# BCM1.net
KiCad netlist of a schematic drawn in Altium Designer
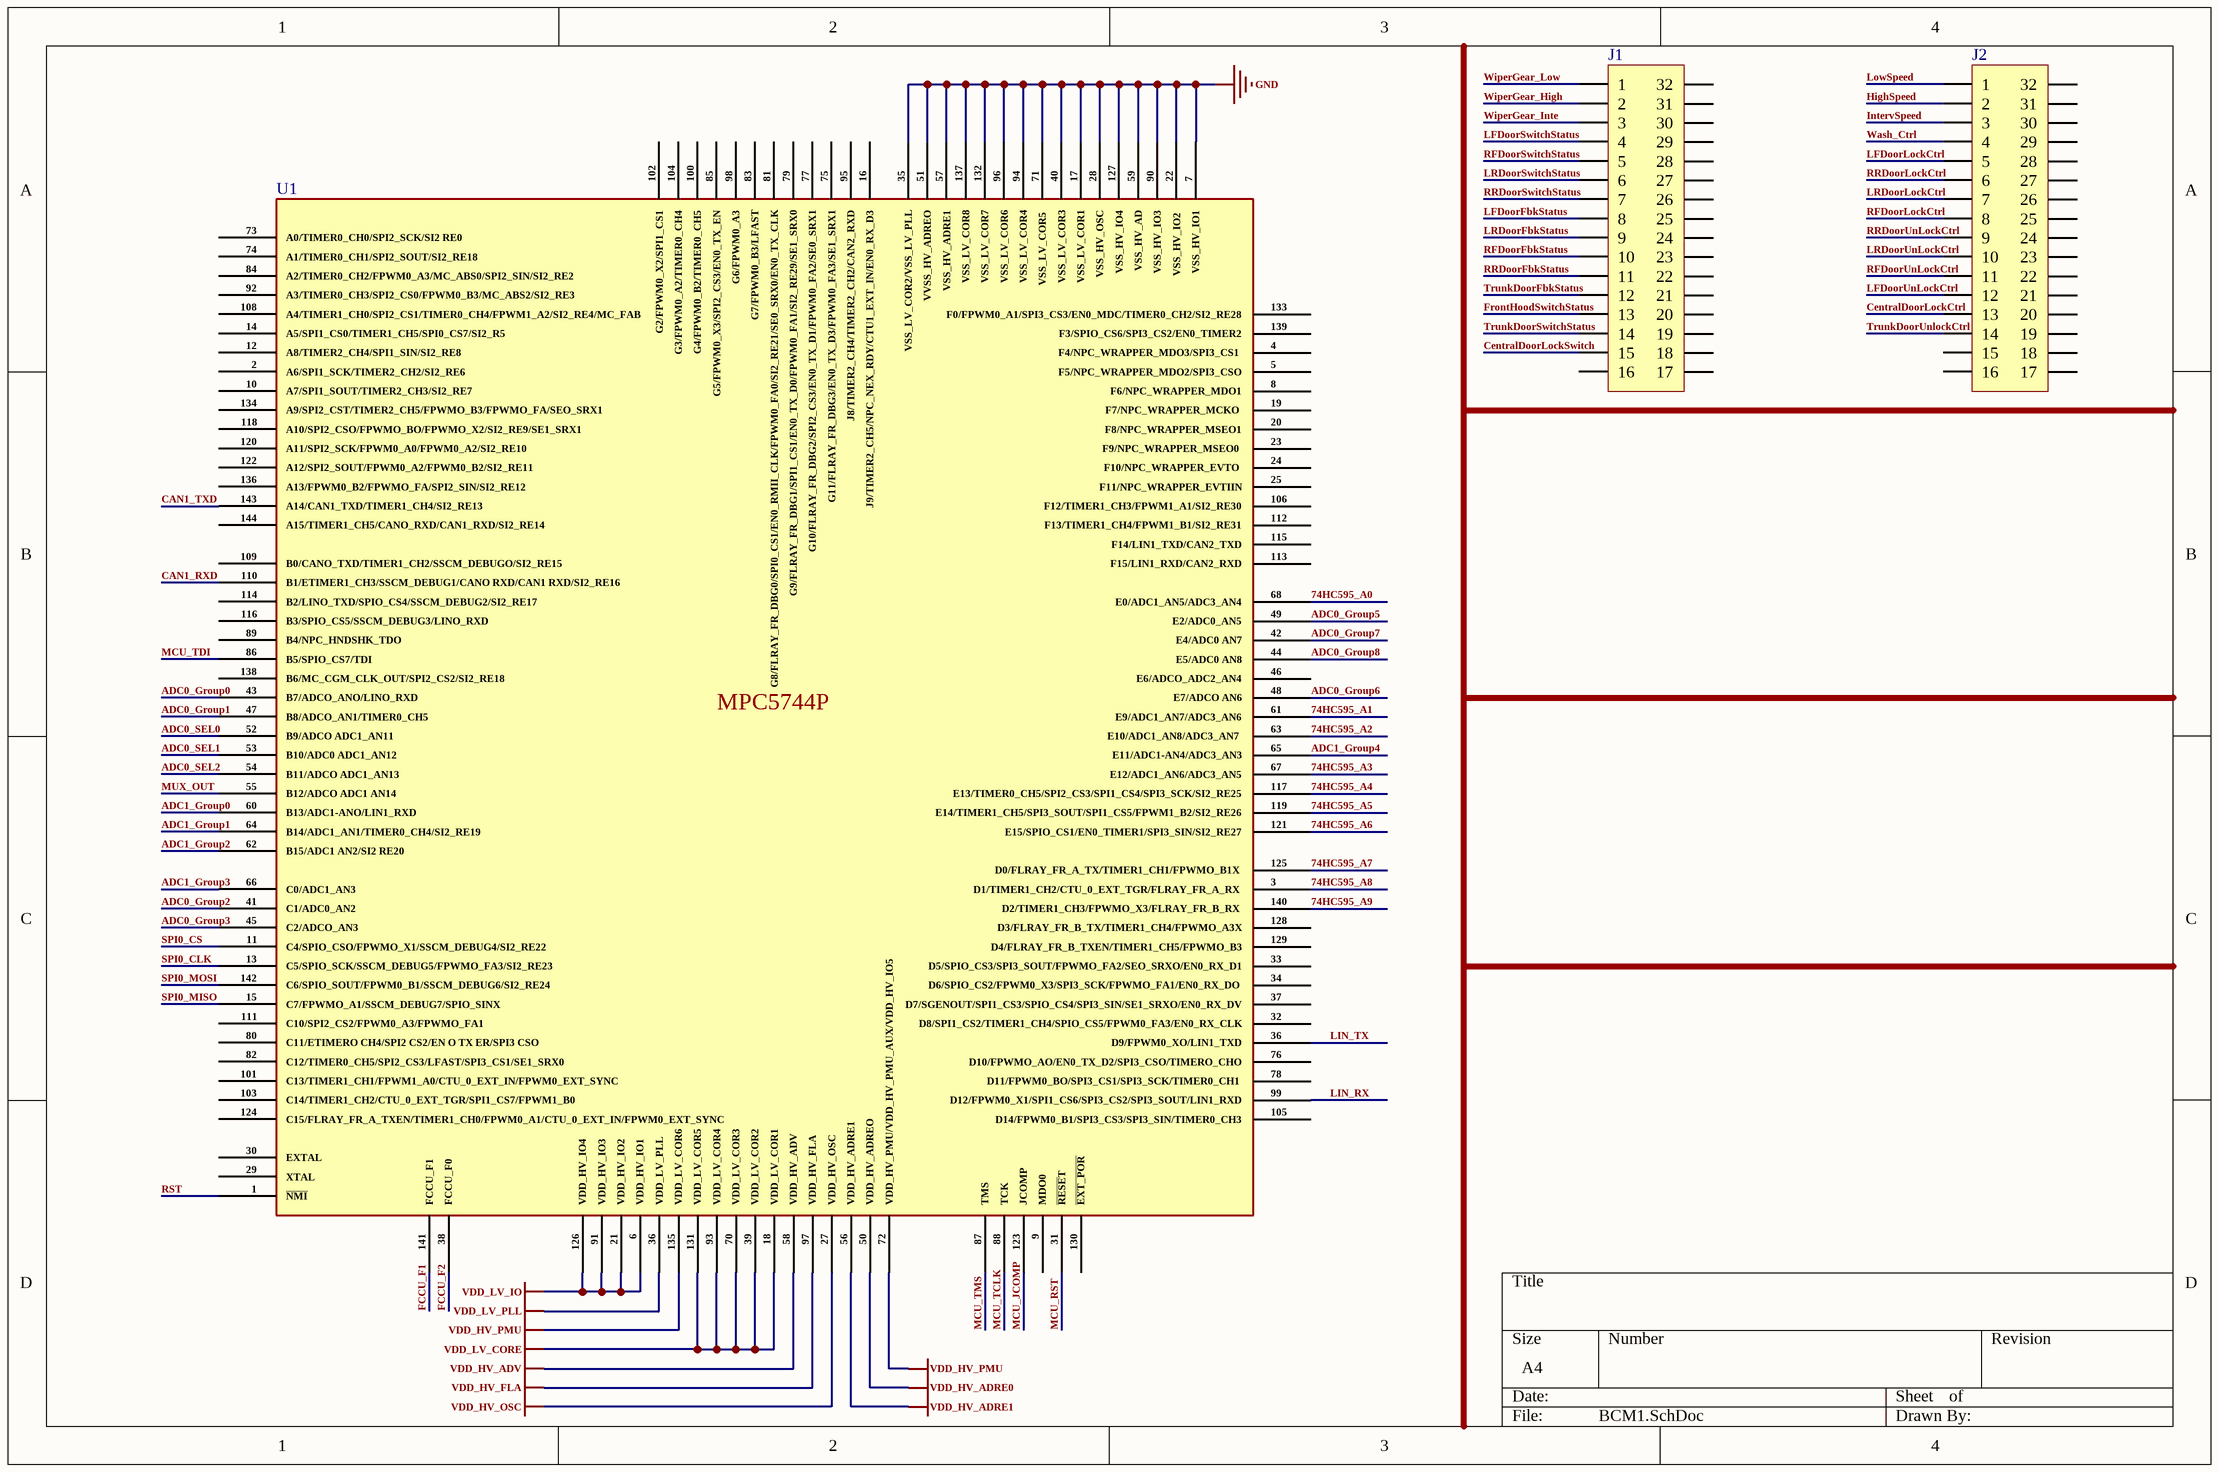
[diagram p0: BCM1.SchDoc]

(export (version "E")
  (design (tool "Eeschema 10.0.6"))
  (components
    (comp (ref "J1") (value "DIP32") (libsource (lib "BCM") (part "DIP32")))
    (comp (ref "J2") (value "DIP32") (libsource (lib "BCM") (part "DIP32")))
    (comp (ref "U1") (value "MPC5744PFK1AMLQ9") (libsource (lib "BCM") (part "MPC5744PFK1AMLQ9")))
  )
  (nets
    (net (code "1") (name "/74HC595_A0") (class "Default")
      (node (ref "U1") (pin "68") (pinfunction "E0/ADC1_AN5/ADC3_AN4_68") (pintype "passive"))
    )
    (net (code "2") (name "/74HC595_A1") (class "Default")
      (node (ref "U1") (pin "61") (pinfunction "E9/ADC1_AN7/ADC3_AN6_61") (pintype "passive"))
    )
    (net (code "3") (name "/74HC595_A2") (class "Default")
      (node (ref "U1") (pin "63") (pinfunction "E10/ADC1_AN8/ADC3_AN7_63") (pintype "passive"))
    )
    (net (code "4") (name "/74HC595_A3") (class "Default")
      (node (ref "U1") (pin "67") (pinfunction "E12/ADC1_AN6/ADC3_AN5_67") (pintype "passive"))
    )
    (net (code "5") (name "/74HC595_A4") (class "Default")
      (node (ref "U1") (pin "117") (pinfunction "E13/TIMER0_CH5/SPI2_CS3/SPI1_CS4/SPI3_SCK/SI2_RE25_117") (pintype "passive"))
    )
    (net (code "6") (name "/74HC595_A5") (class "Default")
      (node (ref "U1") (pin "119") (pinfunction "E14/TIMER1_CH5/SPI3_SOUT/SPI1_CS5/FPWM1_B2/SI2_RE26_119") (pintype "passive"))
    )
    (net (code "7") (name "/74HC595_A6") (class "Default")
      (node (ref "U1") (pin "121") (pinfunction "E15/SPIO_CS1/EN0_TIMER1/SPI3_SIN/SI2_RE27_121") (pintype "passive"))
    )
    (net (code "8") (name "/74HC595_A7") (class "Default")
      (node (ref "U1") (pin "125") (pinfunction "D0/FLRAY_FR_A_TX/TIMER1_CH1/FPWMO_B1X_125") (pintype "passive"))
    )
    (net (code "9") (name "/74HC595_A8") (class "Default")
      (node (ref "U1") (pin "3") (pinfunction "D1/TIMER1_CH2/CTU_0_EXT_TGR/FLRAY_FR_A_RX_3") (pintype "passive"))
    )
    (net (code "10") (name "/74HC595_A9") (class "Default")
      (node (ref "U1") (pin "140") (pinfunction "D2/TIMER1_CH3/FPWMO_X3/FLRAY_FR_B_RX_140") (pintype "passive"))
    )
    (net (code "11") (name "/ADC0_Group0") (class "Default")
      (node (ref "U1") (pin "43") (pinfunction "B7/ADCO_ANO/LINO_RXD_43") (pintype "passive"))
    )
    (net (code "12") (name "/ADC0_Group1") (class "Default")
      (node (ref "U1") (pin "47") (pinfunction "B8/ADCO_AN1/TIMER0_CH5_47") (pintype "passive"))
    )
    (net (code "13") (name "/ADC0_Group2") (class "Default")
      (node (ref "U1") (pin "41") (pinfunction "C1/ADC0_AN2_41") (pintype "passive"))
    )
    (net (code "14") (name "/ADC0_Group3") (class "Default")
      (node (ref "U1") (pin "45") (pinfunction "C2/ADCO_AN3_45") (pintype "passive"))
    )
    (net (code "15") (name "/ADC0_Group5") (class "Default")
      (node (ref "U1") (pin "49") (pinfunction "E2/ADC0_AN5_49") (pintype "passive"))
    )
    (net (code "16") (name "/ADC0_Group6") (class "Default")
      (node (ref "U1") (pin "48") (pinfunction "E7/ADCO_AN6_48") (pintype "passive"))
    )
    (net (code "17") (name "/ADC0_Group7") (class "Default")
      (node (ref "U1") (pin "42") (pinfunction "E4/ADC0_AN7_42") (pintype "passive"))
    )
    (net (code "18") (name "/ADC0_Group8") (class "Default")
      (node (ref "U1") (pin "44") (pinfunction "E5/ADC0_AN8_44") (pintype "passive"))
    )
    (net (code "19") (name "/ADC0_SEL0") (class "Default")
      (node (ref "U1") (pin "52") (pinfunction "B9/ADCO_ADC1_AN11_52") (pintype "passive"))
    )
    (net (code "20") (name "/ADC0_SEL1") (class "Default")
      (node (ref "U1") (pin "53") (pinfunction "B10/ADC0_ADC1_AN12_53") (pintype "passive"))
    )
    (net (code "21") (name "/ADC0_SEL2") (class "Default")
      (node (ref "U1") (pin "54") (pinfunction "B11/ADCO_ADC1_AN13_54") (pintype "passive"))
    )
    (net (code "22") (name "/ADC1_Group0") (class "Default")
      (node (ref "U1") (pin "60") (pinfunction "B13/ADC1-ANO/LIN1_RXD_60") (pintype "passive"))
    )
    (net (code "23") (name "/ADC1_Group1") (class "Default")
      (node (ref "U1") (pin "64") (pinfunction "B14/ADC1_AN1/TIMER0_CH4/SI2_RE19_64") (pintype "passive"))
    )
    (net (code "24") (name "/ADC1_Group2") (class "Default")
      (node (ref "U1") (pin "62") (pinfunction "B15/ADC1_AN2/SI2_RE20_62") (pintype "passive"))
    )
    (net (code "25") (name "/ADC1_Group3") (class "Default")
      (node (ref "U1") (pin "66") (pinfunction "C0/ADC1_AN3_66") (pintype "passive"))
    )
    (net (code "26") (name "/ADC1_Group4") (class "Default")
      (node (ref "U1") (pin "65") (pinfunction "E11/ADC1-AN4/ADC3_AN3_65") (pintype "passive"))
    )
    (net (code "27") (name "/CAN1_RXD") (class "Default")
      (node (ref "U1") (pin "110") (pinfunction "B1/ETIMER1_CH3/SSCM_DEBUG1/CANO_RXD/CAN1_RXD/SI2_RE16_110") (pintype "passive"))
    )
    (net (code "28") (name "/CAN1_TXD") (class "Default")
      (node (ref "U1") (pin "143") (pinfunction "A14/CAN1_TXD/TIMER1_CH4/SI2_RE13_143") (pintype "passive"))
    )
    (net (code "29") (name "/CentralDoorLockCtrl") (class "Default")
      (node (ref "J2") (pin "13") (pinfunction "13_13") (pintype "passive"))
    )
    (net (code "30") (name "/CentralDoorLockSwitch") (class "Default")
      (node (ref "J1") (pin "15") (pinfunction "15_15") (pintype "passive"))
    )
    (net (code "31") (name "/FCCU_F1") (class "Default")
      (node (ref "U1") (pin "141") (pinfunction "FCCU_F1_141") (pintype "passive"))
    )
    (net (code "32") (name "/FCCU_F2") (class "Default")
      (node (ref "U1") (pin "38") (pinfunction "FCCU_F0_38") (pintype "passive"))
    )
    (net (code "33") (name "/FrontHoodSwitchStatus") (class "Default")
      (node (ref "J1") (pin "13") (pinfunction "13_13") (pintype "passive"))
    )
    (net (code "34") (name "/HighSpeed") (class "Default")
      (node (ref "J2") (pin "2") (pinfunction "2_2") (pintype "passive"))
    )
    (net (code "35") (name "/IntervSpeed") (class "Default")
      (node (ref "J2") (pin "3") (pinfunction "3_3") (pintype "passive"))
    )
    (net (code "36") (name "/LFDoorFbkStatus") (class "Default")
      (node (ref "J1") (pin "8") (pinfunction "8_8") (pintype "passive"))
    )
    (net (code "37") (name "/LFDoorLockCtrl") (class "Default")
      (node (ref "J2") (pin "5") (pinfunction "5_5") (pintype "passive"))
    )
    (net (code "38") (name "/LFDoorSwitchStatus") (class "Default")
      (node (ref "J1") (pin "4") (pinfunction "4_4") (pintype "passive"))
    )
    (net (code "39") (name "/LFDoorUnLockCtrl") (class "Default")
      (node (ref "J2") (pin "12") (pinfunction "12_12") (pintype "passive"))
    )
    (net (code "40") (name "/LIN_RX") (class "Default")
      (node (ref "U1") (pin "99") (pinfunction "D12/FPWM0_X1/SPI1_CS6/SPI3_CS2/SPI3_SOUT/LIN1_RXD_99") (pintype "passive"))
    )
    (net (code "41") (name "/LIN_TX") (class "Default")
      (node (ref "U1") (pin "36") (pinfunction "D9/FPWM0_XO/LIN1_TXD_36") (pintype "passive"))
    )
    (net (code "42") (name "/LRDoorFbkStatus") (class "Default")
      (node (ref "J1") (pin "9") (pinfunction "9_9") (pintype "passive"))
    )
    (net (code "43") (name "/LRDoorLockCtrl") (class "Default")
      (node (ref "J2") (pin "7") (pinfunction "7_7") (pintype "passive"))
    )
    (net (code "44") (name "/LRDoorSwitchStatus") (class "Default")
      (node (ref "J1") (pin "6") (pinfunction "6_6") (pintype "passive"))
    )
    (net (code "45") (name "/LRDoorUnLockCtrl") (class "Default")
      (node (ref "J2") (pin "10") (pinfunction "10_10") (pintype "passive"))
    )
    (net (code "46") (name "/LowSpeed") (class "Default")
      (node (ref "J2") (pin "1") (pinfunction "1_1") (pintype "passive"))
    )
    (net (code "47") (name "/MCU_JCOMP") (class "Default")
      (node (ref "U1") (pin "123") (pinfunction "JCOMP_123") (pintype "passive"))
    )
    (net (code "48") (name "/MCU_RST") (class "Default")
      (node (ref "U1") (pin "31") (pinfunction "~{RESE}T_31") (pintype "passive"))
    )
    (net (code "49") (name "/MCU_TCLK") (class "Default")
      (node (ref "U1") (pin "88") (pinfunction "TCK_88") (pintype "passive"))
    )
    (net (code "50") (name "/MCU_TDI") (class "Default")
      (node (ref "U1") (pin "86") (pinfunction "B5/SPIO_CS7/TDI_86") (pintype "passive"))
    )
    (net (code "51") (name "/MCU_TMS") (class "Default")
      (node (ref "U1") (pin "87") (pinfunction "TMS_87") (pintype "passive"))
    )
    (net (code "52") (name "/MUX_OUT") (class "Default")
      (node (ref "U1") (pin "55") (pinfunction "B12/ADCO_ADC1_AN14_55") (pintype "passive"))
    )
    (net (code "53") (name "/RFDoorFbkStatus") (class "Default")
      (node (ref "J1") (pin "10") (pinfunction "10_10") (pintype "passive"))
    )
    (net (code "54") (name "/RFDoorLockCtrl") (class "Default")
      (node (ref "J2") (pin "8") (pinfunction "8_8") (pintype "passive"))
    )
    (net (code "55") (name "/RFDoorSwitchStatus") (class "Default")
      (node (ref "J1") (pin "5") (pinfunction "5_5") (pintype "passive"))
    )
    (net (code "56") (name "/RFDoorUnLockCtrl") (class "Default")
      (node (ref "J2") (pin "11") (pinfunction "11_11") (pintype "passive"))
    )
    (net (code "57") (name "/RRDoorFbkStatus") (class "Default")
      (node (ref "J1") (pin "11") (pinfunction "11_11") (pintype "passive"))
    )
    (net (code "58") (name "/RRDoorLockCtrl") (class "Default")
      (node (ref "J2") (pin "6") (pinfunction "6_6") (pintype "passive"))
    )
    (net (code "59") (name "/RRDoorSwitchStatus") (class "Default")
      (node (ref "J1") (pin "7") (pinfunction "7_7") (pintype "passive"))
    )
    (net (code "60") (name "/RRDoorUnLockCtrl") (class "Default")
      (node (ref "J2") (pin "9") (pinfunction "9_9") (pintype "passive"))
    )
    (net (code "61") (name "/RST") (class "Default")
      (node (ref "U1") (pin "1") (pinfunction "~{NMI}_1") (pintype "passive"))
    )
    (net (code "62") (name "/SPI0_CLK") (class "Default")
      (node (ref "U1") (pin "13") (pinfunction "C5/SPIO_SCK/SSCM_DEBUG5/FPWMO_FA3/SI2_RE23_13") (pintype "passive"))
    )
    (net (code "63") (name "/SPI0_CS") (class "Default")
      (node (ref "U1") (pin "11") (pinfunction "C4/SPIO_CSO/FPWMO_X1/SSCM_DEBUG4/SI2_RE22_11") (pintype "passive"))
    )
    (net (code "64") (name "/SPI0_MISO") (class "Default")
      (node (ref "U1") (pin "15") (pinfunction "C7/FPWMO_A1/SSCM_DEBUG7/SPIO_SINX_15") (pintype "passive"))
    )
    (net (code "65") (name "/SPI0_MOSI") (class "Default")
      (node (ref "U1") (pin "142") (pinfunction "C6/SPIO_SOUT/FPWM0_B1/SSCM_DEBUG6/SI2_RE24_142") (pintype "passive"))
    )
    (net (code "66") (name "/TrunkDoorFbkStatus") (class "Default")
      (node (ref "J1") (pin "12") (pinfunction "12_12") (pintype "passive"))
    )
    (net (code "67") (name "/TrunkDoorSwitchStatus") (class "Default")
      (node (ref "J1") (pin "14") (pinfunction "14_14") (pintype "passive"))
    )
    (net (code "68") (name "/TrunkDoorUnlockCtrl") (class "Default")
      (node (ref "J2") (pin "14") (pinfunction "14_14") (pintype "passive"))
    )
    (net (code "69") (name "/Wash_Ctrl") (class "Default")
      (node (ref "J2") (pin "4") (pinfunction "4_4") (pintype "passive"))
    )
    (net (code "70") (name "/WiperGear_High") (class "Default")
      (node (ref "J1") (pin "2") (pinfunction "2_2") (pintype "passive"))
    )
    (net (code "71") (name "/WiperGear_Inte") (class "Default")
      (node (ref "J1") (pin "3") (pinfunction "3_3") (pintype "passive"))
    )
    (net (code "72") (name "/WiperGear_Low") (class "Default")
      (node (ref "J1") (pin "1") (pinfunction "1_1") (pintype "passive"))
    )
    (net (code "73") (name "GND") (class "Default")
      (node (ref "U1") (pin "127") (pinfunction "VSS_HV_IO4_127") (pintype "passive"))
      (node (ref "U1") (pin "132") (pinfunction "VSS_LV_COR7_132") (pintype "passive"))
      (node (ref "U1") (pin "137") (pinfunction "VSS_LV_COR8_137") (pintype "passive"))
      (node (ref "U1") (pin "17") (pinfunction "VSS_LV_COR1_17") (pintype "passive"))
      (node (ref "U1") (pin "22") (pinfunction "VSS_HV_IO2_22") (pintype "passive"))
      (node (ref "U1") (pin "28") (pinfunction "VSS_HV_OSC_28") (pintype "passive"))
      (node (ref "U1") (pin "35") (pinfunction "VSS_LV_COR2/VSS_LV_PLL_35") (pintype "passive"))
      (node (ref "U1") (pin "40") (pinfunction "VSS_LV_COR3_40") (pintype "passive"))
      (node (ref "U1") (pin "51") (pinfunction "VVSS_HV_ADREO_51") (pintype "passive"))
      (node (ref "U1") (pin "57") (pinfunction "VSS_HV_ADRE1_57") (pintype "passive"))
      (node (ref "U1") (pin "59") (pinfunction "VSS_HV_AD_59") (pintype "passive"))
      (node (ref "U1") (pin "7") (pinfunction "VSS_HV_IO1_7") (pintype "passive"))
      (node (ref "U1") (pin "71") (pinfunction "VSS_LV_COR5_71") (pintype "passive"))
      (node (ref "U1") (pin "90") (pinfunction "VSS_HV_IO3_90") (pintype "passive"))
      (node (ref "U1") (pin "94") (pinfunction "VSS_LV_COR4_94") (pintype "passive"))
      (node (ref "U1") (pin "96") (pinfunction "VSS_LV_COR6_96") (pintype "passive"))
    )
    (net (code "74") (name "VDD_HV_ADRE0") (class "Default")
      (node (ref "U1") (pin "50") (pinfunction "VDD_HV_ADREO_50") (pintype "passive"))
    )
    (net (code "75") (name "VDD_HV_ADRE1") (class "Default")
      (node (ref "U1") (pin "56") (pinfunction "VDD_HV_ADRE1_56") (pintype "passive"))
    )
    (net (code "76") (name "VDD_HV_ADV") (class "Default")
      (node (ref "U1") (pin "58") (pinfunction "VDD_HV_ADV_58") (pintype "passive"))
    )
    (net (code "77") (name "VDD_HV_FLA") (class "Default")
      (node (ref "U1") (pin "97") (pinfunction "VDD_HV_FLA_97") (pintype "passive"))
    )
    (net (code "78") (name "VDD_HV_OSC") (class "Default")
      (node (ref "U1") (pin "27") (pinfunction "VDD_HV_OSC_27") (pintype "passive"))
    )
    (net (code "79") (name "VDD_HV_PMU") (class "Default")
      (node (ref "U1") (pin "135") (pinfunction "VDD_LV_COR6_135") (pintype "passive"))
      (node (ref "U1") (pin "72") (pinfunction "VDD_HV_PMU/VDD_HV_PMU_AUX/VDD_HV_IO5_72") (pintype "passive"))
    )
    (net (code "80") (name "VDD_LV_CORE") (class "Default")
      (node (ref "U1") (pin "131") (pinfunction "VDD_LV_COR5_131") (pintype "passive"))
      (node (ref "U1") (pin "18") (pinfunction "VDD_LV_COR1_18") (pintype "passive"))
      (node (ref "U1") (pin "39") (pinfunction "VDD_LV_COR2_39") (pintype "passive"))
      (node (ref "U1") (pin "70") (pinfunction "VDD_LV_COR3_70") (pintype "passive"))
      (node (ref "U1") (pin "93") (pinfunction "VDD_LV_COR4_93") (pintype "passive"))
    )
    (net (code "81") (name "VDD_LV_IO") (class "Default")
      (node (ref "U1") (pin "126") (pinfunction "VDD_HV_IO4_126") (pintype "passive"))
      (node (ref "U1") (pin "21") (pinfunction "VDD_HV_IO2_21") (pintype "passive"))
      (node (ref "U1") (pin "6") (pinfunction "VDD_HV_IO1_6") (pintype "passive"))
      (node (ref "U1") (pin "91") (pinfunction "VDD_HV_IO3_91") (pintype "passive"))
    )
    (net (code "82") (name "VDD_LV_PLL") (class "Default")
      (node (ref "U1") (pin "36") (pinfunction "VDD_LV_PLL_36") (pintype "passive"))
    )
    (net (code "83") (name "unconnected-(J1-Pad16)") (class "Default")
      (node (ref "J1") (pin "16") (pinfunction "16_16") (pintype "passive"))
    )
    (net (code "84") (name "unconnected-(J1-Pad17)") (class "Default")
      (node (ref "J1") (pin "17") (pinfunction "17_17") (pintype "passive"))
    )
    (net (code "85") (name "unconnected-(J1-Pad18)") (class "Default")
      (node (ref "J1") (pin "18") (pinfunction "18_18") (pintype "passive"))
    )
    (net (code "86") (name "unconnected-(J1-Pad19)") (class "Default")
      (node (ref "J1") (pin "19") (pinfunction "19_19") (pintype "passive"))
    )
    (net (code "87") (name "unconnected-(J1-Pad20)") (class "Default")
      (node (ref "J1") (pin "20") (pinfunction "20_20") (pintype "passive"))
    )
    (net (code "88") (name "unconnected-(J1-Pad21)") (class "Default")
      (node (ref "J1") (pin "21") (pinfunction "21_21") (pintype "passive"))
    )
    (net (code "89") (name "unconnected-(J1-Pad22)") (class "Default")
      (node (ref "J1") (pin "22") (pinfunction "22_22") (pintype "passive"))
    )
    (net (code "90") (name "unconnected-(J1-Pad23)") (class "Default")
      (node (ref "J1") (pin "23") (pinfunction "23_23") (pintype "passive"))
    )
    (net (code "91") (name "unconnected-(J1-Pad24)") (class "Default")
      (node (ref "J1") (pin "24") (pinfunction "24_24") (pintype "passive"))
    )
    (net (code "92") (name "unconnected-(J1-Pad25)") (class "Default")
      (node (ref "J1") (pin "25") (pinfunction "25_25") (pintype "passive"))
    )
    (net (code "93") (name "unconnected-(J1-Pad26)") (class "Default")
      (node (ref "J1") (pin "26") (pinfunction "26_26") (pintype "passive"))
    )
    (net (code "94") (name "unconnected-(J1-Pad27)") (class "Default")
      (node (ref "J1") (pin "27") (pinfunction "27_27") (pintype "passive"))
    )
    (net (code "95") (name "unconnected-(J1-Pad28)") (class "Default")
      (node (ref "J1") (pin "28") (pinfunction "28_28") (pintype "passive"))
    )
    (net (code "96") (name "unconnected-(J1-Pad29)") (class "Default")
      (node (ref "J1") (pin "29") (pinfunction "29_29") (pintype "passive"))
    )
    (net (code "97") (name "unconnected-(J1-Pad30)") (class "Default")
      (node (ref "J1") (pin "30") (pinfunction "30_30") (pintype "passive"))
    )
    (net (code "98") (name "unconnected-(J1-Pad31)") (class "Default")
      (node (ref "J1") (pin "31") (pinfunction "31_31") (pintype "passive"))
    )
    (net (code "99") (name "unconnected-(J1-Pad32)") (class "Default")
      (node (ref "J1") (pin "32") (pinfunction "32_32") (pintype "passive"))
    )
    (net (code "100") (name "unconnected-(J2-Pad15)") (class "Default")
      (node (ref "J2") (pin "15") (pinfunction "15_15") (pintype "passive"))
    )
    (net (code "101") (name "unconnected-(J2-Pad16)") (class "Default")
      (node (ref "J2") (pin "16") (pinfunction "16_16") (pintype "passive"))
    )
    (net (code "102") (name "unconnected-(J2-Pad17)") (class "Default")
      (node (ref "J2") (pin "17") (pinfunction "17_17") (pintype "passive"))
    )
    (net (code "103") (name "unconnected-(J2-Pad18)") (class "Default")
      (node (ref "J2") (pin "18") (pinfunction "18_18") (pintype "passive"))
    )
    (net (code "104") (name "unconnected-(J2-Pad19)") (class "Default")
      (node (ref "J2") (pin "19") (pinfunction "19_19") (pintype "passive"))
    )
    (net (code "105") (name "unconnected-(J2-Pad20)") (class "Default")
      (node (ref "J2") (pin "20") (pinfunction "20_20") (pintype "passive"))
    )
    (net (code "106") (name "unconnected-(J2-Pad21)") (class "Default")
      (node (ref "J2") (pin "21") (pinfunction "21_21") (pintype "passive"))
    )
    (net (code "107") (name "unconnected-(J2-Pad22)") (class "Default")
      (node (ref "J2") (pin "22") (pinfunction "22_22") (pintype "passive"))
    )
    (net (code "108") (name "unconnected-(J2-Pad23)") (class "Default")
      (node (ref "J2") (pin "23") (pinfunction "23_23") (pintype "passive"))
    )
    (net (code "109") (name "unconnected-(J2-Pad24)") (class "Default")
      (node (ref "J2") (pin "24") (pinfunction "24_24") (pintype "passive"))
    )
    (net (code "110") (name "unconnected-(J2-Pad25)") (class "Default")
      (node (ref "J2") (pin "25") (pinfunction "25_25") (pintype "passive"))
    )
    (net (code "111") (name "unconnected-(J2-Pad26)") (class "Default")
      (node (ref "J2") (pin "26") (pinfunction "26_26") (pintype "passive"))
    )
    (net (code "112") (name "unconnected-(J2-Pad27)") (class "Default")
      (node (ref "J2") (pin "27") (pinfunction "27_27") (pintype "passive"))
    )
    (net (code "113") (name "unconnected-(J2-Pad28)") (class "Default")
      (node (ref "J2") (pin "28") (pinfunction "28_28") (pintype "passive"))
    )
    (net (code "114") (name "unconnected-(J2-Pad29)") (class "Default")
      (node (ref "J2") (pin "29") (pinfunction "29_29") (pintype "passive"))
    )
    (net (code "115") (name "unconnected-(J2-Pad30)") (class "Default")
      (node (ref "J2") (pin "30") (pinfunction "30_30") (pintype "passive"))
    )
    (net (code "116") (name "unconnected-(J2-Pad31)") (class "Default")
      (node (ref "J2") (pin "31") (pinfunction "31_31") (pintype "passive"))
    )
    (net (code "117") (name "unconnected-(J2-Pad32)") (class "Default")
      (node (ref "J2") (pin "32") (pinfunction "32_32") (pintype "passive"))
    )
    (net (code "118") (name "unconnected-(U1-A0{slash}TIMER0_CH0{slash}SPI2_SCK{slash}SI2_RE0-Pad73)") (class "Default")
      (node (ref "U1") (pin "73") (pinfunction "A0/TIMER0_CH0/SPI2_SCK/SI2_RE0_73") (pintype "passive"))
    )
    (net (code "119") (name "unconnected-(U1-A1{slash}TIMER0_CH1{slash}SPI2_SOUT{slash}SI2_RE18-Pad74)") (class "Default")
      (node (ref "U1") (pin "74") (pinfunction "A1/TIMER0_CH1/SPI2_SOUT/SI2_RE18_74") (pintype "passive"))
    )
    (net (code "120") (name "unconnected-(U1-A2{slash}TIMER0_CH2{slash}FPWM0_A3{slash}MC_ABS0{slash}SPI2_SIN{slash}SI2_RE2-Pad84)") (class "Default")
      (node (ref "U1") (pin "84") (pinfunction "A2/TIMER0_CH2/FPWM0_A3/MC_ABS0/SPI2_SIN/SI2_RE2_84") (pintype "passive"))
    )
    (net (code "121") (name "unconnected-(U1-A3{slash}TIMER0_CH3{slash}SPI2_CS0{slash}FPWM0_B3{slash}MC_ABS2{slash}SI2_RE3-Pad92)") (class "Default")
      (node (ref "U1") (pin "92") (pinfunction "A3/TIMER0_CH3/SPI2_CS0/FPWM0_B3/MC_ABS2/SI2_RE3_92") (pintype "passive"))
    )
    (net (code "122") (name "unconnected-(U1-A4{slash}TIMER1_CH0{slash}SPI2_CS1{slash}TIMER0_CH4{slash}FPWM1_A2{slash}SI2_RE4{slash}MC_FAB-Pad108)") (class "Default")
      (node (ref "U1") (pin "108") (pinfunction "A4/TIMER1_CH0/SPI2_CS1/TIMER0_CH4/FPWM1_A2/SI2_RE4/MC_FAB_108") (pintype "passive"))
    )
    (net (code "123") (name "unconnected-(U1-A5{slash}SPI1_CS0{slash}TIMER1_CH5{slash}SPI0_CS7{slash}SI2_R5-Pad14)") (class "Default")
      (node (ref "U1") (pin "14") (pinfunction "A5/SPI1_CS0/TIMER1_CH5/SPI0_CS7/SI2_R5_14") (pintype "passive"))
    )
    (net (code "124") (name "unconnected-(U1-A6{slash}SPI1_SCK{slash}TIMER2_CH2{slash}SI2_RE6-Pad2)") (class "Default")
      (node (ref "U1") (pin "2") (pinfunction "A6/SPI1_SCK/TIMER2_CH2/SI2_RE6_2") (pintype "passive"))
    )
    (net (code "125") (name "unconnected-(U1-A7{slash}SPI1_SOUT{slash}TIMER2_CH3{slash}SI2_RE7-Pad10)") (class "Default")
      (node (ref "U1") (pin "10") (pinfunction "A7/SPI1_SOUT/TIMER2_CH3/SI2_RE7_10") (pintype "passive"))
    )
    (net (code "126") (name "unconnected-(U1-A8{slash}TIMER2_CH4{slash}SPI1_SIN{slash}SI2_RE8-Pad12)") (class "Default")
      (node (ref "U1") (pin "12") (pinfunction "A8/TIMER2_CH4/SPI1_SIN/SI2_RE8_12") (pintype "passive"))
    )
    (net (code "127") (name "unconnected-(U1-A9{slash}SPI2_CST{slash}TIMER2_CH5{slash}FPWMO_B3{slash}FPWMO_FA{slash}SEO_SRX1-Pad134)") (class "Default")
      (node (ref "U1") (pin "134") (pinfunction "A9/SPI2_CST/TIMER2_CH5/FPWMO_B3/FPWMO_FA/SEO_SRX1_134") (pintype "passive"))
    )
    (net (code "128") (name "unconnected-(U1-A10{slash}SPI2_CSO{slash}FPWMO_BO{slash}FPWMO_X2{slash}SI2_RE9{slash}SE1_SRX1-Pad118)") (class "Default")
      (node (ref "U1") (pin "118") (pinfunction "A10/SPI2_CSO/FPWMO_BO/FPWMO_X2/SI2_RE9/SE1_SRX1_118") (pintype "passive"))
    )
    (net (code "129") (name "unconnected-(U1-A11{slash}SPI2_SCK{slash}FPWM0_A0{slash}FPWM0_A2{slash}SI2_RE10-Pad120)") (class "Default")
      (node (ref "U1") (pin "120") (pinfunction "A11/SPI2_SCK/FPWM0_A0/FPWM0_A2/SI2_RE10_120") (pintype "passive"))
    )
    (net (code "130") (name "unconnected-(U1-A12{slash}SPI2_SOUT{slash}FPWM0_A2{slash}FPWM0_B2{slash}SI2_RE11-Pad122)") (class "Default")
      (node (ref "U1") (pin "122") (pinfunction "A12/SPI2_SOUT/FPWM0_A2/FPWM0_B2/SI2_RE11_122") (pintype "passive"))
    )
    (net (code "131") (name "unconnected-(U1-A13{slash}FPWM0_B2{slash}FPWMO_FA{slash}SPI2_SIN{slash}SI2_RE12-Pad136)") (class "Default")
      (node (ref "U1") (pin "136") (pinfunction "A13/FPWM0_B2/FPWMO_FA/SPI2_SIN/SI2_RE12_136") (pintype "passive"))
    )
    (net (code "132") (name "unconnected-(U1-A15{slash}TIMER1_CH5{slash}CANO_RXD{slash}CAN1_RXD{slash}SI2_RE14-Pad144)") (class "Default")
      (node (ref "U1") (pin "144") (pinfunction "A15/TIMER1_CH5/CANO_RXD/CAN1_RXD/SI2_RE14_144") (pintype "passive"))
    )
    (net (code "133") (name "unconnected-(U1-B0{slash}CANO_TXD{slash}TIMER1_CH2{slash}SSCM_DEBUGO{slash}SI2_RE15-Pad109)") (class "Default")
      (node (ref "U1") (pin "109") (pinfunction "B0/CANO_TXD/TIMER1_CH2/SSCM_DEBUGO/SI2_RE15_109") (pintype "passive"))
    )
    (net (code "134") (name "unconnected-(U1-B2{slash}LINO_TXD{slash}SPIO_CS4{slash}SSCM_DEBUG2{slash}SI2_RE17-Pad114)") (class "Default")
      (node (ref "U1") (pin "114") (pinfunction "B2/LINO_TXD/SPIO_CS4/SSCM_DEBUG2/SI2_RE17_114") (pintype "passive"))
    )
    (net (code "135") (name "unconnected-(U1-B3{slash}SPIO_CS5{slash}SSCM_DEBUG3{slash}LINO_RXD-Pad116)") (class "Default")
      (node (ref "U1") (pin "116") (pinfunction "B3/SPIO_CS5/SSCM_DEBUG3/LINO_RXD_116") (pintype "passive"))
    )
    (net (code "136") (name "unconnected-(U1-B4{slash}NPC_HNDSHK_TDO-Pad89)") (class "Default")
      (node (ref "U1") (pin "89") (pinfunction "B4/NPC_HNDSHK_TDO_89") (pintype "passive"))
    )
    (net (code "137") (name "unconnected-(U1-B6{slash}MC_CGM_CLK_OUT{slash}SPI2_CS2{slash}SI2_RE18-Pad138)") (class "Default")
      (node (ref "U1") (pin "138") (pinfunction "B6/MC_CGM_CLK_OUT/SPI2_CS2/SI2_RE18_138") (pintype "passive"))
    )
    (net (code "138") (name "unconnected-(U1-C10{slash}SPI2_CS2{slash}FPWM0_A3{slash}FPWMO_FA1-Pad111)") (class "Default")
      (node (ref "U1") (pin "111") (pinfunction "C10/SPI2_CS2/FPWM0_A3/FPWMO_FA1_111") (pintype "passive"))
    )
    (net (code "139") (name "unconnected-(U1-C11{slash}ETIMERO_CH4{slash}SPI2_CS2{slash}EN_O_TX_ER{slash}SPI3_CSO-Pad80)") (class "Default")
      (node (ref "U1") (pin "80") (pinfunction "C11/ETIMERO_CH4/SPI2_CS2/EN_O_TX_ER/SPI3_CSO_80") (pintype "passive"))
    )
    (net (code "140") (name "unconnected-(U1-C12{slash}TIMER0_CH5{slash}SPI2_CS3{slash}LFAST{slash}SPI3_CS1{slash}SE1_SRX0-Pad82)") (class "Default")
      (node (ref "U1") (pin "82") (pinfunction "C12/TIMER0_CH5/SPI2_CS3/LFAST/SPI3_CS1/SE1_SRX0_82") (pintype "passive"))
    )
    (net (code "141") (name "unconnected-(U1-C13{slash}TIMER1_CH1{slash}FPWM1_A0{slash}CTU_0_EXT_IN{slash}FPWM0_EXT_SYNC-Pad101)") (class "Default")
      (node (ref "U1") (pin "101") (pinfunction "C13/TIMER1_CH1/FPWM1_A0/CTU_0_EXT_IN/FPWM0_EXT_SYNC_101") (pintype "passive"))
    )
    (net (code "142") (name "unconnected-(U1-C14{slash}TIMER1_CH2{slash}CTU_0_EXT_TGR{slash}SPI1_CS7{slash}FPWM1_B0-Pad103)") (class "Default")
      (node (ref "U1") (pin "103") (pinfunction "C14/TIMER1_CH2/CTU_0_EXT_TGR/SPI1_CS7/FPWM1_B0_103") (pintype "passive"))
    )
    (net (code "143") (name "unconnected-(U1-C15{slash}FLRAY_FR_A_TXEN{slash}TIMER1_CH0{slash}FPWM0_A1{slash}CTU_0_EXT_IN{slash}FPWM0_EXT_SYNC-Pad124)") (class "Default")
      (node (ref "U1") (pin "124") (pinfunction "C15/FLRAY_FR_A_TXEN/TIMER1_CH0/FPWM0_A1/CTU_0_EXT_IN/FPWM0_EXT_SYNC_124") (pintype "passive"))
    )
    (net (code "144") (name "unconnected-(U1-D3{slash}FLRAY_FR_B_TX{slash}TIMER1_CH4{slash}FPWMO_A3X-Pad128)") (class "Default")
      (node (ref "U1") (pin "128") (pinfunction "D3/FLRAY_FR_B_TX/TIMER1_CH4/FPWMO_A3X_128") (pintype "passive"))
    )
    (net (code "145") (name "unconnected-(U1-D4{slash}FLRAY_FR_B_TXEN{slash}TIMER1_CH5{slash}FPWMO_B3-Pad129)") (class "Default")
      (node (ref "U1") (pin "129") (pinfunction "D4/FLRAY_FR_B_TXEN/TIMER1_CH5/FPWMO_B3_129") (pintype "passive"))
    )
    (net (code "146") (name "unconnected-(U1-D5{slash}SPIO_CS3{slash}SPI3_SOUT{slash}FPWMO_FA2{slash}SEO_SRXO{slash}EN0_RX_D1-Pad33)") (class "Default")
      (node (ref "U1") (pin "33") (pinfunction "D5/SPIO_CS3/SPI3_SOUT/FPWMO_FA2/SEO_SRXO/EN0_RX_D1_33") (pintype "passive"))
    )
    (net (code "147") (name "unconnected-(U1-D6{slash}SPIO_CS2{slash}FPWM0_X3{slash}SPI3_SCK{slash}FPWMO_FA1{slash}EN0_RX_DO-Pad34)") (class "Default")
      (node (ref "U1") (pin "34") (pinfunction "D6/SPIO_CS2/FPWM0_X3/SPI3_SCK/FPWMO_FA1/EN0_RX_DO_34") (pintype "passive"))
    )
    (net (code "148") (name "unconnected-(U1-D7{slash}SGENOUT{slash}SPI1_CS3{slash}SPIO_CS4{slash}SPI3_SIN{slash}SE1_SRXO{slash}EN0_RX_DV-Pad37)") (class "Default")
      (node (ref "U1") (pin "37") (pinfunction "D7/SGENOUT/SPI1_CS3/SPIO_CS4/SPI3_SIN/SE1_SRXO/EN0_RX_DV_37") (pintype "passive"))
    )
    (net (code "149") (name "unconnected-(U1-D8{slash}SPI1_CS2{slash}TIMER1_CH4{slash}SPIO_CS5{slash}FPWM0_FA3{slash}EN0_RX_CLK-Pad32)") (class "Default")
      (node (ref "U1") (pin "32") (pinfunction "D8/SPI1_CS2/TIMER1_CH4/SPIO_CS5/FPWM0_FA3/EN0_RX_CLK_32") (pintype "passive"))
    )
    (net (code "150") (name "unconnected-(U1-D10{slash}FPWMO_AO{slash}EN0_TX_D2{slash}SPI3_CSO{slash}TIMERO_CHO-Pad76)") (class "Default")
      (node (ref "U1") (pin "76") (pinfunction "D10/FPWMO_AO/EN0_TX_D2/SPI3_CSO/TIMERO_CHO_76") (pintype "passive"))
    )
    (net (code "151") (name "unconnected-(U1-D11{slash}FPWM0_BO{slash}SPI3_CS1{slash}SPI3_SCK{slash}TIMER0_CH1-Pad78)") (class "Default")
      (node (ref "U1") (pin "78") (pinfunction "D11/FPWM0_BO/SPI3_CS1/SPI3_SCK/TIMER0_CH1_78") (pintype "passive"))
    )
    (net (code "152") (name "unconnected-(U1-D14{slash}FPWM0_B1{slash}SPI3_CS3{slash}SPI3_SIN{slash}TIMER0_CH3-Pad105)") (class "Default")
      (node (ref "U1") (pin "105") (pinfunction "D14/FPWM0_B1/SPI3_CS3/SPI3_SIN/TIMER0_CH3_105") (pintype "passive"))
    )
    (net (code "153") (name "unconnected-(U1-E6{slash}ADCO_ADC2_AN4-Pad46)") (class "Default")
      (node (ref "U1") (pin "46") (pinfunction "E6/ADCO_ADC2_AN4_46") (pintype "passive"))
    )
    (net (code "154") (name "unconnected-(U1-EXTAL-Pad30)") (class "Default")
      (node (ref "U1") (pin "30") (pinfunction "EXTAL_30") (pintype "passive"))
    )
    (net (code "155") (name "unconnected-(U1-F0{slash}FPWM0_A1{slash}SPI3_CS3{slash}EN0_MDC{slash}TIMER0_CH2{slash}SI2_RE28-Pad133)") (class "Default")
      (node (ref "U1") (pin "133") (pinfunction "F0/FPWM0_A1/SPI3_CS3/EN0_MDC/TIMER0_CH2/SI2_RE28_133") (pintype "passive"))
    )
    (net (code "156") (name "unconnected-(U1-F3{slash}SPIO_CS6{slash}SPI3_CS2{slash}EN0_TIMER2-Pad139)") (class "Default")
      (node (ref "U1") (pin "139") (pinfunction "F3/SPIO_CS6/SPI3_CS2/EN0_TIMER2_139") (pintype "passive"))
    )
    (net (code "157") (name "unconnected-(U1-F4{slash}NPC_WRAPPER_MDO3{slash}SPI3_CS1-Pad4)") (class "Default")
      (node (ref "U1") (pin "4") (pinfunction "F4/NPC_WRAPPER_MDO3/SPI3_CS1_4") (pintype "passive"))
    )
    (net (code "158") (name "unconnected-(U1-F5{slash}NPC_WRAPPER_MDO2{slash}SPI3_CSO-Pad5)") (class "Default")
      (node (ref "U1") (pin "5") (pinfunction "F5/NPC_WRAPPER_MDO2/SPI3_CSO_5") (pintype "passive"))
    )
    (net (code "159") (name "unconnected-(U1-F6{slash}NPC_WRAPPER_MDO1-Pad8)") (class "Default")
      (node (ref "U1") (pin "8") (pinfunction "F6/NPC_WRAPPER_MDO1_8") (pintype "passive"))
    )
    (net (code "160") (name "unconnected-(U1-F7{slash}NPC_WRAPPER_MCKO-Pad19)") (class "Default")
      (node (ref "U1") (pin "19") (pinfunction "F7/NPC_WRAPPER_MCKO_19") (pintype "passive"))
    )
    (net (code "161") (name "unconnected-(U1-F8{slash}NPC_WRAPPER_MSEO1-Pad20)") (class "Default")
      (node (ref "U1") (pin "20") (pinfunction "F8/NPC_WRAPPER_MSEO1_20") (pintype "passive"))
    )
    (net (code "162") (name "unconnected-(U1-F9{slash}NPC_WRAPPER_MSEO0-Pad23)") (class "Default")
      (node (ref "U1") (pin "23") (pinfunction "F9/NPC_WRAPPER_MSEO0_23") (pintype "passive"))
    )
    (net (code "163") (name "unconnected-(U1-F10{slash}NPC_WRAPPER_EVTO-Pad24)") (class "Default")
      (node (ref "U1") (pin "24") (pinfunction "F10/NPC_WRAPPER_EVTO_24") (pintype "passive"))
    )
    (net (code "164") (name "unconnected-(U1-F11{slash}NPC_WRAPPER_EVTIIN-Pad25)") (class "Default")
      (node (ref "U1") (pin "25") (pinfunction "F11/NPC_WRAPPER_EVTIIN_25") (pintype "passive"))
    )
    (net (code "165") (name "unconnected-(U1-F12{slash}TIMER1_CH3{slash}FPWM1_A1{slash}SI2_RE30-Pad106)") (class "Default")
      (node (ref "U1") (pin "106") (pinfunction "F12/TIMER1_CH3/FPWM1_A1/SI2_RE30_106") (pintype "passive"))
    )
    (net (code "166") (name "unconnected-(U1-F13{slash}TIMER1_CH4{slash}FPWM1_B1{slash}SI2_RE31-Pad112)") (class "Default")
      (node (ref "U1") (pin "112") (pinfunction "F13/TIMER1_CH4/FPWM1_B1/SI2_RE31_112") (pintype "passive"))
    )
    (net (code "167") (name "unconnected-(U1-F14{slash}LIN1_TXD{slash}CAN2_TXD-Pad115)") (class "Default")
      (node (ref "U1") (pin "115") (pinfunction "F14/LIN1_TXD/CAN2_TXD_115") (pintype "passive"))
    )
    (net (code "168") (name "unconnected-(U1-F15{slash}LIN1_RXD{slash}CAN2_RXD-Pad113)") (class "Default")
      (node (ref "U1") (pin "113") (pinfunction "F15/LIN1_RXD/CAN2_RXD_113") (pintype "passive"))
    )
    (net (code "169") (name "unconnected-(U1-G2{slash}FPWM0_X2{slash}SPI1_CS1-Pad102)") (class "Default")
      (node (ref "U1") (pin "102") (pinfunction "G2/FPWM0_X2/SPI1_CS1_102") (pintype "passive"))
    )
    (net (code "170") (name "unconnected-(U1-G3{slash}FPWM0_A2{slash}TIMER0_CH4-Pad104)") (class "Default")
      (node (ref "U1") (pin "104") (pinfunction "G3/FPWM0_A2/TIMER0_CH4_104") (pintype "passive"))
    )
    (net (code "171") (name "unconnected-(U1-G4{slash}FPWM0_B2{slash}TIMER0_CH5-Pad100)") (class "Default")
      (node (ref "U1") (pin "100") (pinfunction "G4/FPWM0_B2/TIMER0_CH5_100") (pintype "passive"))
    )
    (net (code "172") (name "unconnected-(U1-G5{slash}FPWM0_X3{slash}SPI2_CS3{slash}EN0_TX_EN-Pad85)") (class "Default")
      (node (ref "U1") (pin "85") (pinfunction "G5/FPWM0_X3/SPI2_CS3/EN0_TX_EN_85") (pintype "passive"))
    )
    (net (code "173") (name "unconnected-(U1-G6{slash}FPWM0_A3-Pad98)") (class "Default")
      (node (ref "U1") (pin "98") (pinfunction "G6/FPWM0_A3_98") (pintype "passive"))
    )
    (net (code "174") (name "unconnected-(U1-G7{slash}FPWM0_B3{slash}LFAST-Pad83)") (class "Default")
      (node (ref "U1") (pin "83") (pinfunction "G7/FPWM0_B3/LFAST_83") (pintype "passive"))
    )
    (net (code "175") (name "unconnected-(U1-G8{slash}FLRAY_FR_DBG0{slash}SPI0_CS1{slash}EN0_RMII_CLK{slash}FPWM0_FA0{slash}SI2_RE21{slash}SE0_SRX0{slash}EN0_TX_CLK-Pad81)") (class "Default")
      (node (ref "U1") (pin "81") (pinfunction "G8/FLRAY_FR_DBG0/SPI0_CS1/EN0_RMII_CLK/FPWM0_FA0/SI2_RE21/SE0_SRX0/EN0_TX_CLK_81") (pintype "passive"))
    )
    (net (code "176") (name "unconnected-(U1-G9{slash}FLRAY_FR_DBG1{slash}SPI1_CS1{slash}EN0_TX_D0{slash}FPWM0_FA1{slash}SI2_RE29{slash}SE1_SRX0-Pad79)") (class "Default")
      (node (ref "U1") (pin "79") (pinfunction "G9/FLRAY_FR_DBG1/SPI1_CS1/EN0_TX_D0/FPWM0_FA1/SI2_RE29/SE1_SRX0_79") (pintype "passive"))
    )
    (net (code "177") (name "unconnected-(U1-G10{slash}FLRAY_FR_DBG2{slash}SPI2_CS3{slash}EN0_TX_D1{slash}FPWM0_FA2{slash}SE0_SRX1-Pad77)") (class "Default")
      (node (ref "U1") (pin "77") (pinfunction "G10/FLRAY_FR_DBG2/SPI2_CS3/EN0_TX_D1/FPWM0_FA2/SE0_SRX1_77") (pintype "passive"))
    )
    (net (code "178") (name "unconnected-(U1-G11{slash}FLRAY_FR_DBG3{slash}EN0_TX_D3{slash}FPWM0_FA3{slash}SE1_SRX1-Pad75)") (class "Default")
      (node (ref "U1") (pin "75") (pinfunction "G11/FLRAY_FR_DBG3/EN0_TX_D3/FPWM0_FA3/SE1_SRX1_75") (pintype "passive"))
    )
    (net (code "179") (name "unconnected-(U1-J8{slash}TIMER2_CH4{slash}TIMER2_CH2{slash}CAN2_RXD-Pad95)") (class "Default")
      (node (ref "U1") (pin "95") (pinfunction "J8/TIMER2_CH4/TIMER2_CH2/CAN2_RXD_95") (pintype "passive"))
    )
    (net (code "180") (name "unconnected-(U1-J9{slash}TIMER2_CH5{slash}NPC_NEX_RDY{slash}CTU1_EXT_IN{slash}EN0_RX_D3-Pad16)") (class "Default")
      (node (ref "U1") (pin "16") (pinfunction "J9/TIMER2_CH5/NPC_NEX_RDY/CTU1_EXT_IN/EN0_RX_D3_16") (pintype "passive"))
    )
    (net (code "181") (name "unconnected-(U1-MDO0-Pad9)") (class "Default")
      (node (ref "U1") (pin "9") (pinfunction "MDO0_9") (pintype "passive"))
    )
    (net (code "182") (name "unconnected-(U1-XTAL-Pad29)") (class "Default")
      (node (ref "U1") (pin "29") (pinfunction "XTAL_29") (pintype "passive"))
    )
    (net (code "183") (name "unconnected-(U1-~{EXT_POR}-Pad130)") (class "Default")
      (node (ref "U1") (pin "130") (pinfunction "~{EXT_POR}_130") (pintype "passive"))
    )
  )
)
